# Brigid_control_board.net
KiCad netlist of a schematic drawn in EAGLE
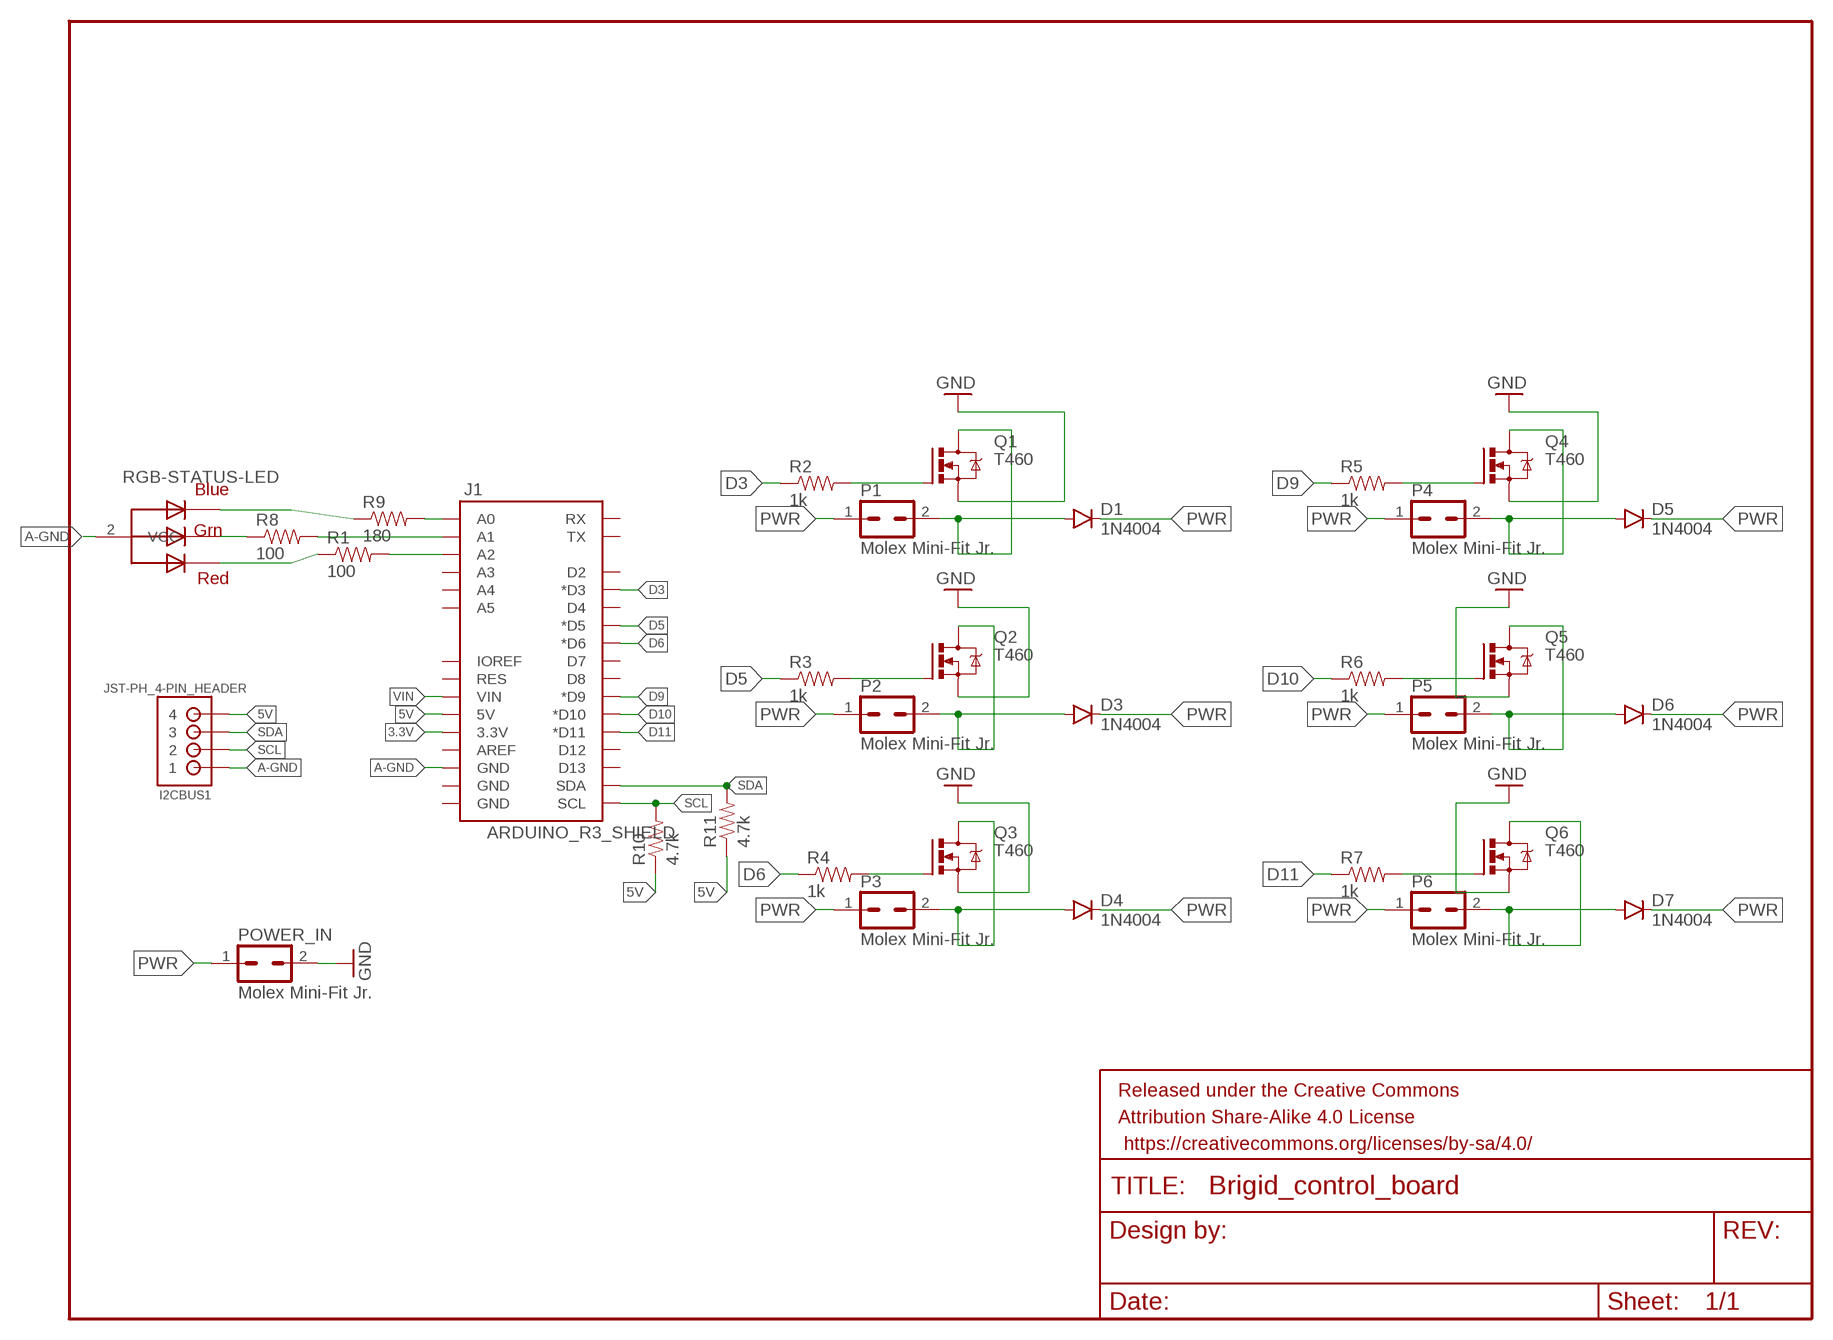
[diagram p0: schematic, sheet 1]

(export (version "E")
  (design (tool "Eeschema 10.0.6"))
  (components
    (comp (ref "D1")
      (value "1N4004")
      (footprint "eagle-import:DIODE-1N4001")
      (libsource (lib "eagle-import") (part "DIODEPTH"))
    )
    (comp (ref "D3")
      (value "1N4004")
      (footprint "eagle-import:DIODE-1N4001")
      (libsource (lib "eagle-import") (part "DIODEPTH"))
    )
    (comp (ref "D4")
      (value "1N4004")
      (footprint "eagle-import:DIODE-1N4001")
      (libsource (lib "eagle-import") (part "DIODEPTH"))
    )
    (comp (ref "D5")
      (value "1N4004")
      (footprint "eagle-import:DIODE-1N4001")
      (libsource (lib "eagle-import") (part "DIODEPTH"))
    )
    (comp (ref "D6")
      (value "1N4004")
      (footprint "eagle-import:DIODE-1N4001")
      (libsource (lib "eagle-import") (part "DIODEPTH"))
    )
    (comp (ref "D7")
      (value "1N4004")
      (footprint "eagle-import:DIODE-1N4001")
      (libsource (lib "eagle-import") (part "DIODEPTH"))
    )
    (comp (ref "FRAME1")
      (value "FRAME-LETTER")
      (footprint "eagle-import:CREATIVE_COMMONS")
      (libsource (lib "eagle-import") (part "FRAME-LETTER"))
    )
    (comp (ref "I2CBUS1")
      (value "JST-PH_4-PIN_HEADER")
      (footprint "eagle-import:JST_B4B-PH_HEADER")
      (libsource (lib "eagle-import") (part "JST-PH_4-PIN_HEADER"))
    )
    (comp (ref "J1")
      (value "ARDUINO_R3_SHIELD")
      (footprint "eagle-import:UNO_R3_SHIELD")
      (libsource (lib "eagle-import") (part "ARDUINO_R3_SHIELD"))
    )
    (comp (ref "P1")
      (value "Molex Mini-Fit Jr.")
      (footprint "eagle-import:39-30-_02_")
      (libsource (lib "eagle-import") (part "39-30-?02?"))
    )
    (comp (ref "P2")
      (value "Molex Mini-Fit Jr.")
      (footprint "eagle-import:39-30-_02_")
      (libsource (lib "eagle-import") (part "39-30-?02?"))
    )
    (comp (ref "P3")
      (value "Molex Mini-Fit Jr.")
      (footprint "eagle-import:39-30-_02_")
      (libsource (lib "eagle-import") (part "39-30-?02?"))
    )
    (comp (ref "P4")
      (value "Molex Mini-Fit Jr.")
      (footprint "eagle-import:39-30-_02_")
      (libsource (lib "eagle-import") (part "39-30-?02?"))
    )
    (comp (ref "P5")
      (value "Molex Mini-Fit Jr.")
      (footprint "eagle-import:39-30-_02_")
      (libsource (lib "eagle-import") (part "39-30-?02?"))
    )
    (comp (ref "P6")
      (value "Molex Mini-Fit Jr.")
      (footprint "eagle-import:39-30-_02_")
      (libsource (lib "eagle-import") (part "39-30-?02?"))
    )
    (comp (ref "POWER_IN")
      (value "Molex Mini-Fit Jr.")
      (footprint "eagle-import:39-30-_02_")
      (libsource (lib "eagle-import") (part "39-30-?02?"))
    )
    (comp (ref "Q1")
      (value "T460")
      (footprint "eagle-import:TO220BV")
      (libsource (lib "eagle-import") (part "IRF540"))
    )
    (comp (ref "Q2")
      (value "T460")
      (footprint "eagle-import:TO220BV")
      (libsource (lib "eagle-import") (part "IRF540"))
    )
    (comp (ref "Q3")
      (value "T460")
      (footprint "eagle-import:TO220BV")
      (libsource (lib "eagle-import") (part "IRF540"))
    )
    (comp (ref "Q4")
      (value "T460")
      (footprint "eagle-import:TO220BV")
      (libsource (lib "eagle-import") (part "IRF540"))
    )
    (comp (ref "Q5")
      (value "T460")
      (footprint "eagle-import:TO220BV")
      (libsource (lib "eagle-import") (part "IRF540"))
    )
    (comp (ref "Q6")
      (value "T460")
      (footprint "eagle-import:TO220BV")
      (libsource (lib "eagle-import") (part "IRF540"))
    )
    (comp (ref "R1")
      (value "100")
      (footprint "eagle-import:AXIAL-0.3EZ")
      (libsource (lib "eagle-import") (part "RESISTOREZ"))
    )
    (comp (ref "R2")
      (value "1k")
      (footprint "eagle-import:AXIAL-0.3EZ")
      (libsource (lib "eagle-import") (part "RESISTOREZ"))
    )
    (comp (ref "R3")
      (value "1k")
      (footprint "eagle-import:AXIAL-0.3EZ")
      (libsource (lib "eagle-import") (part "RESISTOREZ"))
    )
    (comp (ref "R4")
      (value "1k")
      (footprint "eagle-import:AXIAL-0.3EZ")
      (libsource (lib "eagle-import") (part "RESISTOREZ"))
    )
    (comp (ref "R5")
      (value "1k")
      (footprint "eagle-import:AXIAL-0.3EZ")
      (libsource (lib "eagle-import") (part "RESISTOREZ"))
    )
    (comp (ref "R6")
      (value "1k")
      (footprint "eagle-import:AXIAL-0.3EZ")
      (libsource (lib "eagle-import") (part "RESISTOREZ"))
    )
    (comp (ref "R7")
      (value "1k")
      (footprint "eagle-import:AXIAL-0.3EZ")
      (libsource (lib "eagle-import") (part "RESISTOREZ"))
    )
    (comp (ref "R8")
      (value "100")
      (footprint "eagle-import:AXIAL-0.3EZ")
      (libsource (lib "eagle-import") (part "RESISTOREZ"))
    )
    (comp (ref "R9")
      (value "180")
      (footprint "eagle-import:AXIAL-0.3EZ")
      (libsource (lib "eagle-import") (part "RESISTOREZ"))
    )
    (comp (ref "R10")
      (value "4.7k")
      (footprint "eagle-import:AXIAL-0.3EZ")
      (libsource (lib "eagle-import") (part "RESISTOREZ"))
    )
    (comp (ref "R11")
      (value "4.7k")
      (footprint "eagle-import:AXIAL-0.3EZ")
      (libsource (lib "eagle-import") (part "RESISTOREZ"))
    )
    (comp (ref "RGB-STATUS-LED")
      (value "RGB LED")
      (footprint "eagle-import:LED5MMRGB")
      (libsource (lib "eagle-import") (part "RGBLED_CA"))
    )
  )
  (nets
    (net (code "1") (name "3.3V") (class "Default")
      (node (ref "J1") (pin "3.3V") (pinfunction "3.3V_3.3V") (pintype "bidirectional"))
    )
    (net (code "2") (name "5V") (class "Default")
      (node (ref "I2CBUS1") (pin "P4") (pinfunction "4_P4") (pintype "bidirectional"))
      (node (ref "J1") (pin "5V") (pinfunction "5V_5V") (pintype "bidirectional"))
      (node (ref "R10") (pin "P$1") (pinfunction "1_P$1") (pintype "passive"))
      (node (ref "R11") (pin "P$1") (pinfunction "1_P$1") (pintype "passive"))
    )
    (net (code "3") (name "A-GND") (class "Default")
      (node (ref "I2CBUS1") (pin "P1") (pinfunction "1_P1") (pintype "bidirectional"))
      (node (ref "J1") (pin "GND@2") (pinfunction "GND_GND@2") (pintype "bidirectional"))
      (node (ref "RGB-STATUS-LED") (pin "2") (pinfunction "VCC_2") (pintype "bidirectional"))
    )
    (net (code "4") (name "D3") (class "Default")
      (node (ref "J1") (pin "D3") (pinfunction "*D3_D3") (pintype "bidirectional"))
      (node (ref "R2") (pin "P$1") (pinfunction "1_P$1") (pintype "passive"))
    )
    (net (code "5") (name "D5") (class "Default")
      (node (ref "J1") (pin "D5") (pinfunction "*D5_D5") (pintype "bidirectional"))
      (node (ref "R3") (pin "P$1") (pinfunction "1_P$1") (pintype "passive"))
    )
    (net (code "6") (name "D6") (class "Default")
      (node (ref "J1") (pin "D6") (pinfunction "*D6_D6") (pintype "bidirectional"))
      (node (ref "R4") (pin "P$1") (pinfunction "1_P$1") (pintype "passive"))
    )
    (net (code "7") (name "D9") (class "Default")
      (node (ref "J1") (pin "D9") (pinfunction "*D9_D9") (pintype "bidirectional"))
      (node (ref "R5") (pin "P$1") (pinfunction "1_P$1") (pintype "passive"))
    )
    (net (code "8") (name "D10") (class "Default")
      (node (ref "J1") (pin "D10") (pinfunction "*D10_D10") (pintype "bidirectional"))
      (node (ref "R6") (pin "P$1") (pinfunction "1_P$1") (pintype "passive"))
    )
    (net (code "9") (name "D11") (class "Default")
      (node (ref "J1") (pin "D11") (pinfunction "*D11_D11") (pintype "bidirectional"))
      (node (ref "R7") (pin "P$1") (pinfunction "1_P$1") (pintype "passive"))
    )
    (net (code "10") (name "GND") (class "Default")
      (node (ref "POWER_IN") (pin "2") (pinfunction "2_2") (pintype "passive"))
      (node (ref "Q1") (pin "S") (pinfunction "S_S") (pintype "passive"))
      (node (ref "Q2") (pin "S") (pinfunction "S_S") (pintype "passive"))
      (node (ref "Q3") (pin "S") (pinfunction "S_S") (pintype "passive"))
      (node (ref "Q4") (pin "S") (pinfunction "S_S") (pintype "passive"))
      (node (ref "Q5") (pin "S") (pinfunction "S_S") (pintype "passive"))
      (node (ref "Q6") (pin "S") (pinfunction "S_S") (pintype "passive"))
    )
    (net (code "11") (name "Net-(D1-PadA)") (class "Default")
      (node (ref "D1") (pin "A") (pinfunction "A_A") (pintype "passive"))
      (node (ref "P1") (pin "2") (pinfunction "2_2") (pintype "passive"))
      (node (ref "Q1") (pin "D") (pinfunction "D_D") (pintype "passive"))
    )
    (net (code "12") (name "Net-(D3-PadA)") (class "Default")
      (node (ref "D3") (pin "A") (pinfunction "A_A") (pintype "passive"))
      (node (ref "P2") (pin "2") (pinfunction "2_2") (pintype "passive"))
      (node (ref "Q2") (pin "D") (pinfunction "D_D") (pintype "passive"))
    )
    (net (code "13") (name "Net-(D4-PadA)") (class "Default")
      (node (ref "D4") (pin "A") (pinfunction "A_A") (pintype "passive"))
      (node (ref "P3") (pin "2") (pinfunction "2_2") (pintype "passive"))
      (node (ref "Q3") (pin "D") (pinfunction "D_D") (pintype "passive"))
    )
    (net (code "14") (name "Net-(D5-PadA)") (class "Default")
      (node (ref "D5") (pin "A") (pinfunction "A_A") (pintype "passive"))
      (node (ref "P4") (pin "2") (pinfunction "2_2") (pintype "passive"))
      (node (ref "Q4") (pin "D") (pinfunction "D_D") (pintype "passive"))
    )
    (net (code "15") (name "Net-(D6-PadA)") (class "Default")
      (node (ref "D6") (pin "A") (pinfunction "A_A") (pintype "passive"))
      (node (ref "P5") (pin "2") (pinfunction "2_2") (pintype "passive"))
      (node (ref "Q5") (pin "D") (pinfunction "D_D") (pintype "passive"))
    )
    (net (code "16") (name "Net-(D7-PadA)") (class "Default")
      (node (ref "D7") (pin "A") (pinfunction "A_A") (pintype "passive"))
      (node (ref "P6") (pin "2") (pinfunction "2_2") (pintype "passive"))
      (node (ref "Q6") (pin "D") (pinfunction "D_D") (pintype "passive"))
    )
    (net (code "17") (name "Net-(R1-1)") (class "Default")
      (node (ref "R1") (pin "P$1") (pinfunction "1_P$1") (pintype "passive"))
      (node (ref "RGB-STATUS-LED") (pin "1") (pinfunction "RED_1") (pintype "bidirectional"))
    )
    (net (code "18") (name "Net-(R1-2)") (class "Default")
      (node (ref "J1") (pin "A2") (pinfunction "A2_A2") (pintype "bidirectional"))
      (node (ref "R1") (pin "P$2") (pinfunction "2_P$2") (pintype "passive"))
    )
    (net (code "19") (name "Net-(R2-2)") (class "Default")
      (node (ref "Q1") (pin "G") (pinfunction "G_G") (pintype "passive"))
      (node (ref "R2") (pin "P$2") (pinfunction "2_P$2") (pintype "passive"))
    )
    (net (code "20") (name "Net-(R3-2)") (class "Default")
      (node (ref "Q2") (pin "G") (pinfunction "G_G") (pintype "passive"))
      (node (ref "R3") (pin "P$2") (pinfunction "2_P$2") (pintype "passive"))
    )
    (net (code "21") (name "Net-(R4-2)") (class "Default")
      (node (ref "Q3") (pin "G") (pinfunction "G_G") (pintype "passive"))
      (node (ref "R4") (pin "P$2") (pinfunction "2_P$2") (pintype "passive"))
    )
    (net (code "22") (name "Net-(R5-2)") (class "Default")
      (node (ref "Q4") (pin "G") (pinfunction "G_G") (pintype "passive"))
      (node (ref "R5") (pin "P$2") (pinfunction "2_P$2") (pintype "passive"))
    )
    (net (code "23") (name "Net-(R6-2)") (class "Default")
      (node (ref "Q5") (pin "G") (pinfunction "G_G") (pintype "passive"))
      (node (ref "R6") (pin "P$2") (pinfunction "2_P$2") (pintype "passive"))
    )
    (net (code "24") (name "Net-(R7-2)") (class "Default")
      (node (ref "Q6") (pin "G") (pinfunction "G_G") (pintype "passive"))
      (node (ref "R7") (pin "P$2") (pinfunction "2_P$2") (pintype "passive"))
    )
    (net (code "25") (name "Net-(R8-1)") (class "Default")
      (node (ref "R8") (pin "P$1") (pinfunction "1_P$1") (pintype "passive"))
      (node (ref "RGB-STATUS-LED") (pin "3") (pinfunction "GREEN_3") (pintype "bidirectional"))
    )
    (net (code "26") (name "Net-(R8-2)") (class "Default")
      (node (ref "J1") (pin "A1") (pinfunction "A1_A1") (pintype "bidirectional"))
      (node (ref "R8") (pin "P$2") (pinfunction "2_P$2") (pintype "passive"))
    )
    (net (code "27") (name "Net-(R9-1)") (class "Default")
      (node (ref "R9") (pin "P$1") (pinfunction "1_P$1") (pintype "passive"))
      (node (ref "RGB-STATUS-LED") (pin "4") (pinfunction "BLUE_4") (pintype "bidirectional"))
    )
    (net (code "28") (name "Net-(R9-2)") (class "Default")
      (node (ref "J1") (pin "A0") (pinfunction "A0_A0") (pintype "bidirectional"))
      (node (ref "R9") (pin "P$2") (pinfunction "2_P$2") (pintype "passive"))
    )
    (net (code "29") (name "PWR") (class "Default")
      (node (ref "D1") (pin "C") (pinfunction "C_C") (pintype "passive"))
      (node (ref "D3") (pin "C") (pinfunction "C_C") (pintype "passive"))
      (node (ref "D4") (pin "C") (pinfunction "C_C") (pintype "passive"))
      (node (ref "D5") (pin "C") (pinfunction "C_C") (pintype "passive"))
      (node (ref "D6") (pin "C") (pinfunction "C_C") (pintype "passive"))
      (node (ref "D7") (pin "C") (pinfunction "C_C") (pintype "passive"))
      (node (ref "P1") (pin "1") (pinfunction "1_1") (pintype "passive"))
      (node (ref "P2") (pin "1") (pinfunction "1_1") (pintype "passive"))
      (node (ref "P3") (pin "1") (pinfunction "1_1") (pintype "passive"))
      (node (ref "P4") (pin "1") (pinfunction "1_1") (pintype "passive"))
      (node (ref "P5") (pin "1") (pinfunction "1_1") (pintype "passive"))
      (node (ref "P6") (pin "1") (pinfunction "1_1") (pintype "passive"))
      (node (ref "POWER_IN") (pin "1") (pinfunction "1_1") (pintype "passive"))
    )
    (net (code "30") (name "SCL") (class "Default")
      (node (ref "I2CBUS1") (pin "P2") (pinfunction "2_P2") (pintype "bidirectional"))
      (node (ref "J1") (pin "SCL") (pinfunction "SCL_SCL") (pintype "bidirectional"))
      (node (ref "R10") (pin "P$2") (pinfunction "2_P$2") (pintype "passive"))
    )
    (net (code "31") (name "SDA") (class "Default")
      (node (ref "I2CBUS1") (pin "P3") (pinfunction "3_P3") (pintype "bidirectional"))
      (node (ref "J1") (pin "SDA") (pinfunction "SDA_SDA") (pintype "bidirectional"))
      (node (ref "R11") (pin "P$2") (pinfunction "2_P$2") (pintype "passive"))
    )
    (net (code "32") (name "VIN") (class "Default")
      (node (ref "J1") (pin "VIN") (pinfunction "VIN_VIN") (pintype "bidirectional"))
    )
    (net (code "33") (name "unconnected-(J1-GND-PadGND@0)") (class "Default")
      (node (ref "J1") (pin "GND@0") (pinfunction "GND_GND@0") (pintype "bidirectional"))
    )
    (net (code "34") (name "unconnected-(J1-GND-PadGND@1)") (class "Default")
      (node (ref "J1") (pin "GND@1") (pinfunction "GND_GND@1") (pintype "bidirectional"))
    )
    (net (code "35") (name "unconnected-(J1-PadA3)") (class "Default")
      (node (ref "J1") (pin "A3") (pinfunction "A3_A3") (pintype "bidirectional"))
    )
    (net (code "36") (name "unconnected-(J1-PadA4)") (class "Default")
      (node (ref "J1") (pin "A4") (pinfunction "A4_A4") (pintype "bidirectional"))
    )
    (net (code "37") (name "unconnected-(J1-PadA5)") (class "Default")
      (node (ref "J1") (pin "A5") (pinfunction "A5_A5") (pintype "bidirectional"))
    )
    (net (code "38") (name "unconnected-(J1-PadAREF)") (class "Default")
      (node (ref "J1") (pin "AREF") (pinfunction "AREF_AREF") (pintype "bidirectional"))
    )
    (net (code "39") (name "unconnected-(J1-PadD2)") (class "Default")
      (node (ref "J1") (pin "D2") (pinfunction "D2_D2") (pintype "bidirectional"))
    )
    (net (code "40") (name "unconnected-(J1-PadD4)") (class "Default")
      (node (ref "J1") (pin "D4") (pinfunction "D4_D4") (pintype "bidirectional"))
    )
    (net (code "41") (name "unconnected-(J1-PadD7)") (class "Default")
      (node (ref "J1") (pin "D7") (pinfunction "D7_D7") (pintype "bidirectional"))
    )
    (net (code "42") (name "unconnected-(J1-PadD8)") (class "Default")
      (node (ref "J1") (pin "D8") (pinfunction "D8_D8") (pintype "bidirectional"))
    )
    (net (code "43") (name "unconnected-(J1-PadD12)") (class "Default")
      (node (ref "J1") (pin "D12") (pinfunction "D12_D12") (pintype "bidirectional"))
    )
    (net (code "44") (name "unconnected-(J1-PadD13)") (class "Default")
      (node (ref "J1") (pin "D13") (pinfunction "D13_D13") (pintype "bidirectional"))
    )
    (net (code "45") (name "unconnected-(J1-PadIOREF)") (class "Default")
      (node (ref "J1") (pin "IOREF") (pinfunction "IOREF_IOREF") (pintype "bidirectional"))
    )
    (net (code "46") (name "unconnected-(J1-PadRES)") (class "Default")
      (node (ref "J1") (pin "RES") (pinfunction "RES_RES") (pintype "bidirectional"))
    )
    (net (code "47") (name "unconnected-(J1-PadRX)") (class "Default")
      (node (ref "J1") (pin "RX") (pinfunction "RX_RX") (pintype "bidirectional"))
    )
    (net (code "48") (name "unconnected-(J1-PadTX)") (class "Default")
      (node (ref "J1") (pin "TX") (pinfunction "TX_TX") (pintype "bidirectional"))
    )
  )
)
